# FMC_connector.net
KiCad netlist of a schematic drawn in Altium Designer
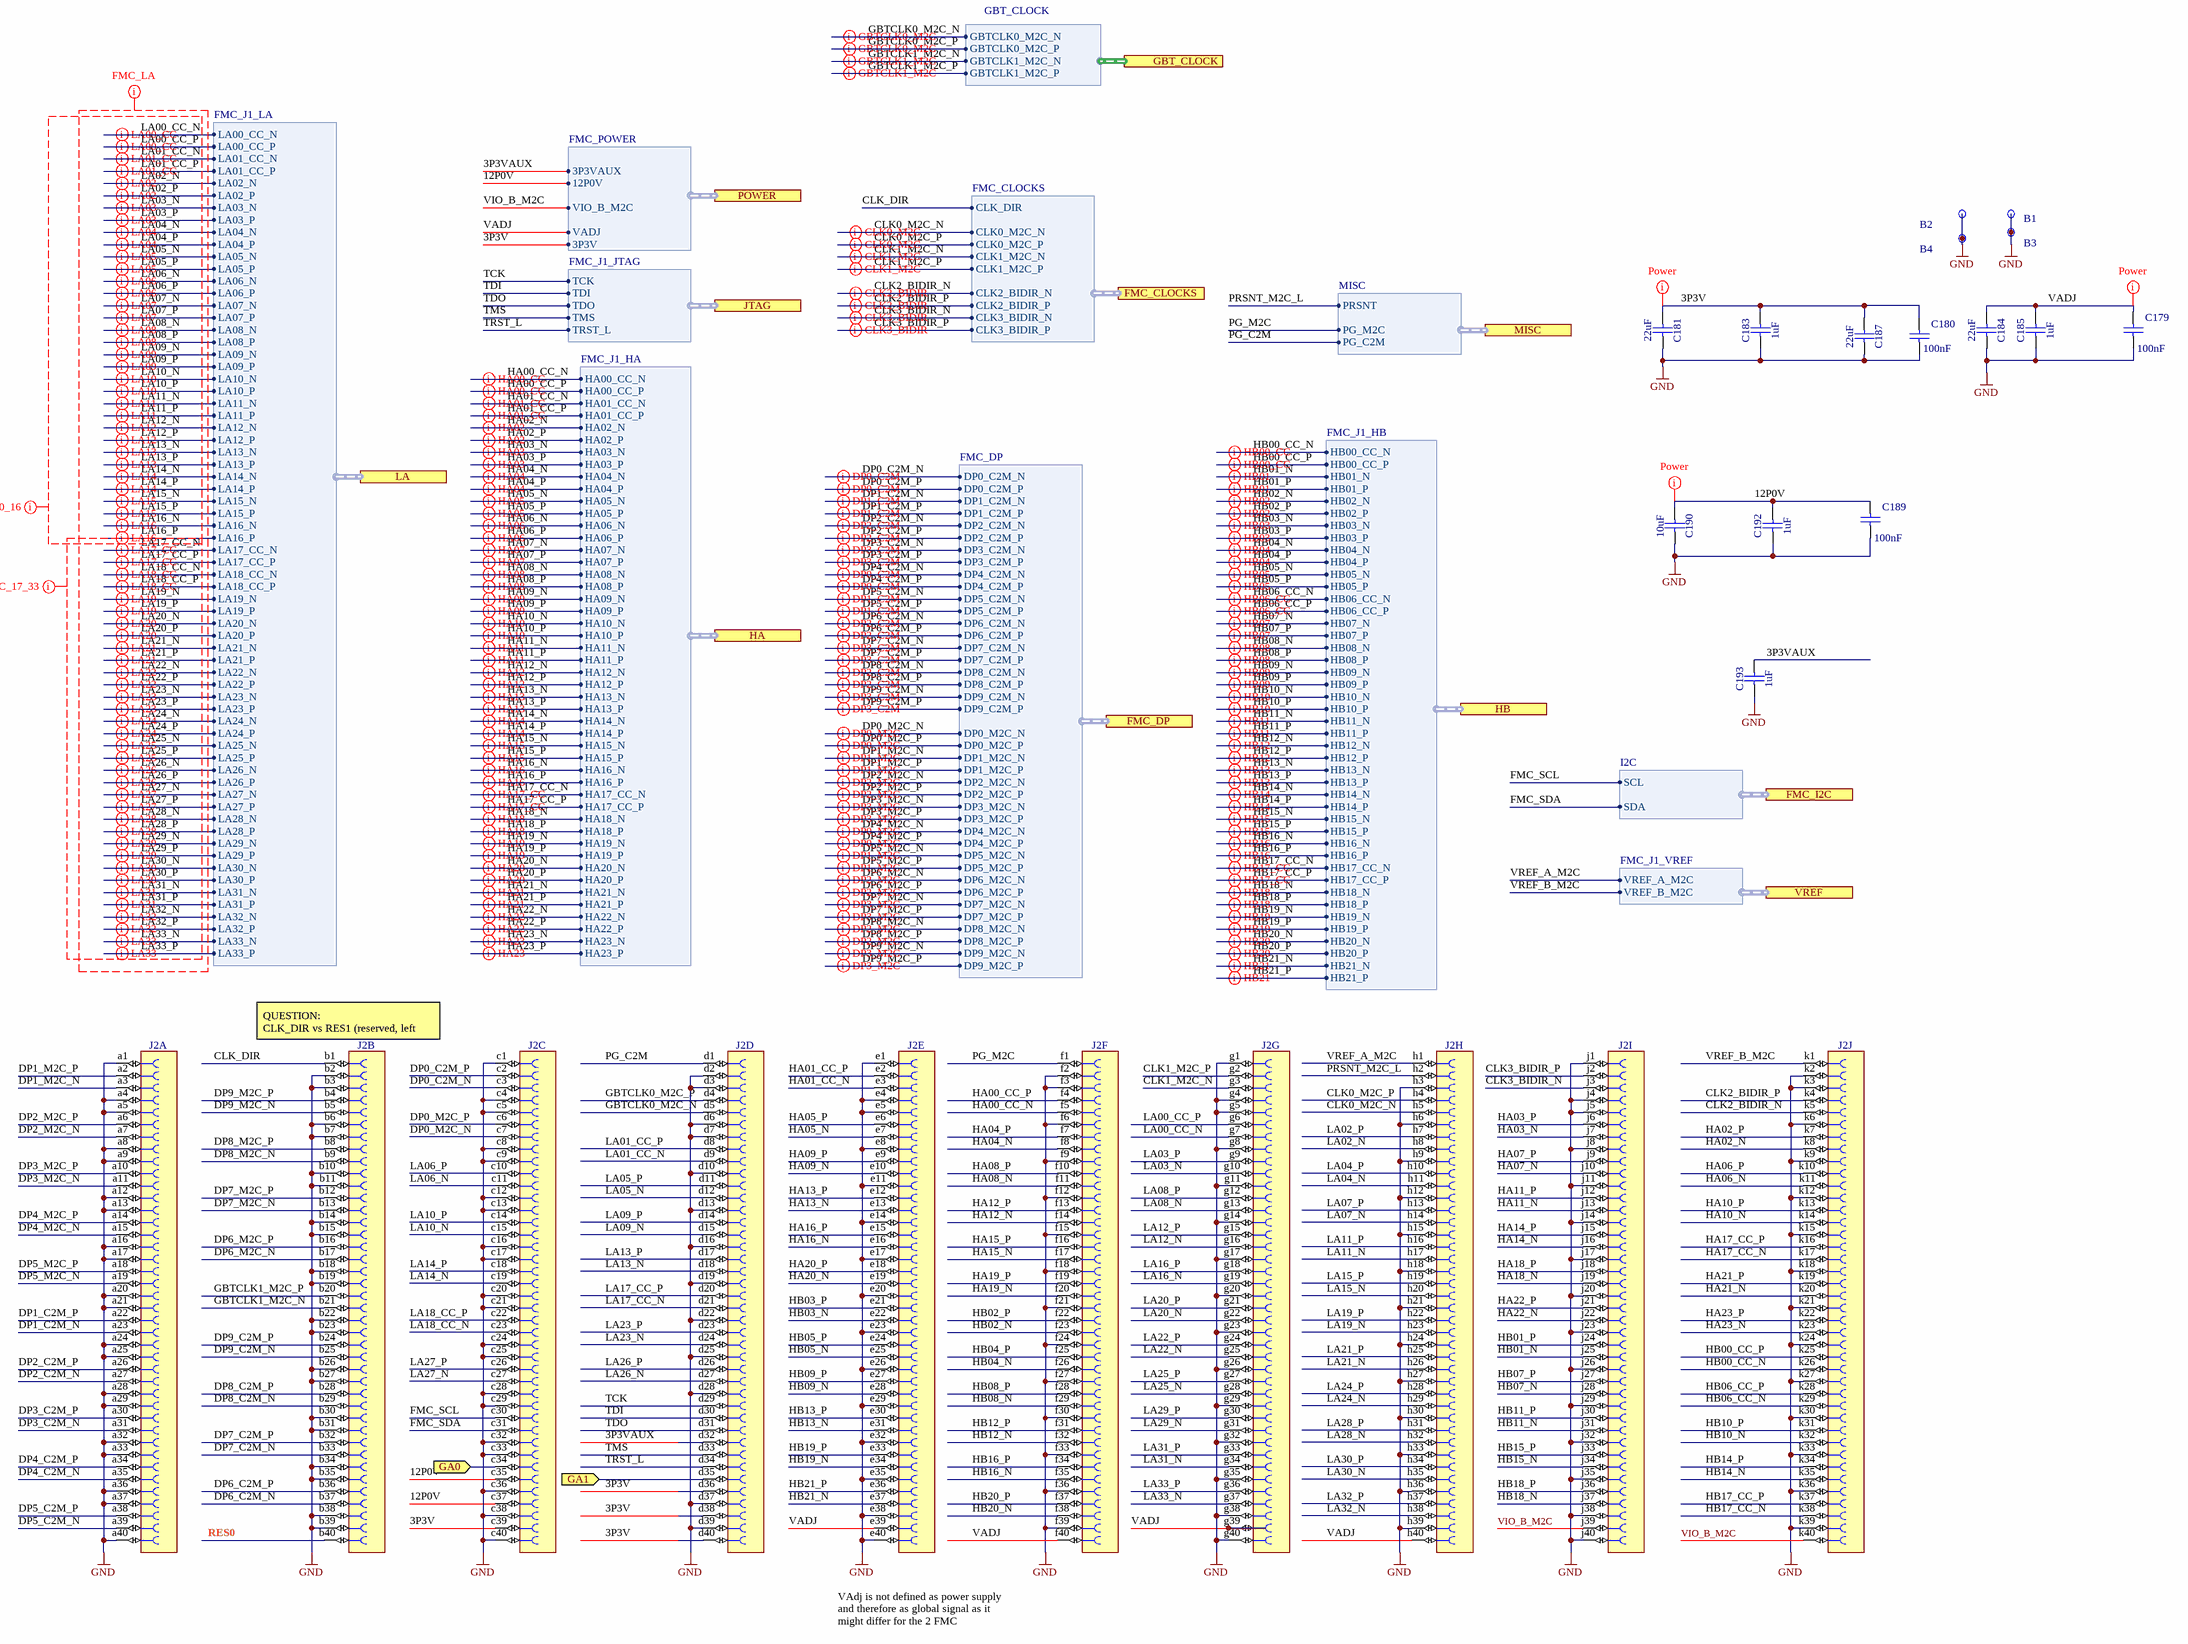
[diagram p0: FMC_connector.SchDoc]

(export (version "E")
  (design (tool "Eeschema 10.0.6"))
  (components
    (comp (ref "B1")
      (value "Plated Hole")
      (footprint "MTG270_500")
      (description "Single Terminal Socket")
      (fields (field (name "PART NUMBER") "PLATED_HOLE2.7_PAD5.0") (field (name "AUTHOR") "CERN DEM JMW"))
      (libsource (lib "Eletro-mechanical") (part "Single Terminal Socket"))
    )
    (comp (ref "B2")
      (value "Plated Hole")
      (footprint "MTG270_500")
      (description "Single Terminal Socket")
      (fields (field (name "PART NUMBER") "PLATED_HOLE2.7_PAD5.0") (field (name "AUTHOR") "CERN DEM JMW"))
      (libsource (lib "Eletro-mechanical") (part "Single Terminal Socket"))
    )
    (comp (ref "B3")
      (value "Plated Hole")
      (footprint "MTG270_500")
      (description "Single Terminal Socket")
      (fields (field (name "PART NUMBER") "PLATED_HOLE2.7_PAD5.0") (field (name "AUTHOR") "CERN DEM JMW"))
      (libsource (lib "Eletro-mechanical") (part "Single Terminal Socket"))
    )
    (comp (ref "B4")
      (value "Plated Hole")
      (footprint "MTG270_500")
      (description "Single Terminal Socket")
      (fields (field (name "PART NUMBER") "PLATED_HOLE2.7_PAD5.0") (field (name "AUTHOR") "CERN DEM JMW"))
      (libsource (lib "Eletro-mechanical") (part "Single Terminal Socket"))
    )
    (comp (ref "C179")
      (value "100nF")
      (footprint "CAPC0603X33N")
      (description "Non-polarised capacitor")
      (fields
        (field (name "PART NUMBER") "CC0201_100NF_6.3V_10%_X5R")
        (field (name "VOLTAGE") "6.3V")
        (field (name "AUTHOR") "CERN DEM JLC")
      )
      (libsource (lib "Capacitors") (part "Capacitor - non polarized"))
    )
    (comp (ref "C180")
      (value "100nF")
      (footprint "CAPC0603X33N")
      (description "Non-polarised capacitor")
      (fields
        (field (name "PART NUMBER") "CC0201_100NF_6.3V_10%_X5R")
        (field (name "VOLTAGE") "6.3V")
        (field (name "AUTHOR") "CERN DEM JLC")
      )
      (libsource (lib "Capacitors") (part "Capacitor - non polarized"))
    )
    (comp (ref "C181")
      (value "22uF")
      (footprint "CAPC3216X180N")
      (description "Non-polarised capacitor")
      (fields
        (field (name "PART NUMBER") "CC1206_22UF_10V_10%_X7R")
        (field (name "VOLTAGE") "10V")
        (field (name "AUTHOR") "CERN DEM JLC")
      )
      (libsource (lib "Capacitors") (part "Capacitor - non polarized"))
    )
    (comp (ref "C183")
      (value "1uF")
      (footprint "CAPC1608X87N")
      (description "Non-polarised capacitor")
      (fields
        (field (name "PART NUMBER") "CC0603_1UF_25V_10%_X7R")
        (field (name "VOLTAGE") "25V")
        (field (name "AUTHOR") "CERN DEM JLC")
      )
      (libsource (lib "Capacitors") (part "Capacitor - non polarized"))
    )
    (comp (ref "C184")
      (value "22uF")
      (footprint "CAPC3216X180N")
      (description "Non-polarised capacitor")
      (fields
        (field (name "PART NUMBER") "CC1206_22UF_10V_10%_X7R")
        (field (name "VOLTAGE") "10V")
        (field (name "AUTHOR") "CERN DEM JLC")
      )
      (libsource (lib "Capacitors") (part "Capacitor - non polarized"))
    )
    (comp (ref "C185")
      (value "1uF")
      (footprint "CAPC1608X87N")
      (description "Non-polarised capacitor")
      (fields
        (field (name "PART NUMBER") "CC0603_1UF_25V_10%_X7R")
        (field (name "VOLTAGE") "25V")
        (field (name "AUTHOR") "CERN DEM JLC")
      )
      (libsource (lib "Capacitors") (part "Capacitor - non polarized"))
    )
    (comp (ref "C187")
      (value "22uF")
      (footprint "CAPC3216X180N")
      (description "Non-polarised capacitor")
      (fields
        (field (name "PART NUMBER") "CC1206_22UF_10V_10%_X7R")
        (field (name "VOLTAGE") "10V")
        (field (name "AUTHOR") "CERN DEM JLC")
      )
      (libsource (lib "Capacitors") (part "Capacitor - non polarized"))
    )
    (comp (ref "C189")
      (value "100nF")
      (footprint "CAPC0603X33N")
      (description "Non-polarised capacitor")
      (fields
        (field (name "PART NUMBER") "CC0201_100NF_6.3V_10%_X5R")
        (field (name "VOLTAGE") "6.3V")
        (field (name "AUTHOR") "CERN DEM JLC")
      )
      (libsource (lib "Capacitors") (part "Capacitor - non polarized"))
    )
    (comp (ref "C190")
      (value "10uF")
      (footprint "CAPC2012X135N")
      (description "Non-polarised capacitor")
      (fields
        (field (name "PART NUMBER") "CC0805_10UF_16V_10%_X5R")
        (field (name "VOLTAGE") "16V")
        (field (name "AUTHOR") "CERN DEM JLC")
      )
      (libsource (lib "Capacitors") (part "Capacitor - non polarized"))
    )
    (comp (ref "C192")
      (value "1uF")
      (footprint "CAPC1608X87N")
      (description "Non-polarised capacitor")
      (fields
        (field (name "PART NUMBER") "CC0603_1UF_25V_10%_X7R")
        (field (name "VOLTAGE") "25V")
        (field (name "AUTHOR") "CERN DEM JLC")
      )
      (libsource (lib "Capacitors") (part "Capacitor - non polarized"))
    )
    (comp (ref "C193")
      (value "1uF")
      (footprint "CAPC1608X87N")
      (description "Non-polarised capacitor")
      (fields
        (field (name "PART NUMBER") "CC0603_1UF_25V_10%_X7R")
        (field (name "VOLTAGE") "25V")
        (field (name "AUTHOR") "CERN DEM JLC")
      )
      (libsource (lib "Capacitors") (part "Capacitor - non polarized"))
    )
    (comp (ref "J2")
      (value "VITA 57")
      (footprint "SAMTEC_ASP-134486-01")
      (description "Connector VITA 57, 400 Female contacts in 10 row abcdefghj")
      (fields
        (field (name "PART NUMBER") "SAMTEC_ASP-134486-01")
        (field (name "MANUFACTURER") "SAMTEC")
        (field (name "AUTHOR") "CERN DEM JLC")
      )
      (libsource (lib "Connectors") (part "Connector VITA 57 400 Female (abcdefghjk)"))
    )
  )
  (nets
    (net (code "12") (name "/3P3V") (class "Default")
      (node (ref "C180") (pin "2") (pinfunction "2_2") (pintype "passive"))
      (node (ref "C181") (pin "1") (pinfunction "1_1") (pintype "passive"))
      (node (ref "C183") (pin "2") (pinfunction "2_2") (pintype "passive"))
      (node (ref "C187") (pin "1") (pinfunction "1_1") (pintype "passive"))
      (node (ref "J2") (pin "c39") (pinfunction "c39_c39") (pintype "bidirectional"))
      (node (ref "J2") (pin "d36") (pinfunction "d36_d36") (pintype "bidirectional"))
      (node (ref "J2") (pin "d38") (pinfunction "d38_d38") (pintype "bidirectional"))
      (node (ref "J2") (pin "d40") (pinfunction "d40_d40") (pintype "bidirectional"))
    )
    (net (code "13") (name "/3P3VAUX") (class "Default")
      (node (ref "C193") (pin "2") (pinfunction "2_2") (pintype "passive"))
      (node (ref "J2") (pin "d32") (pinfunction "d32_d32") (pintype "bidirectional"))
    )
    (net (code "14") (name "/12P0V") (class "Default")
      (node (ref "C189") (pin "2") (pinfunction "2_2") (pintype "passive"))
      (node (ref "C190") (pin "1") (pinfunction "1_1") (pintype "passive"))
      (node (ref "C192") (pin "2") (pinfunction "2_2") (pintype "passive"))
      (node (ref "J2") (pin "c35") (pinfunction "c35_c35") (pintype "bidirectional"))
      (node (ref "J2") (pin "c37") (pinfunction "c37_c37") (pintype "bidirectional"))
    )
    (net (code "15") (name "/CLK0_M2C_N") (class "Default")
      (node (ref "J2") (pin "h5") (pinfunction "h5_h5") (pintype "bidirectional"))
    )
    (net (code "16") (name "/CLK0_M2C_P") (class "Default")
      (node (ref "J2") (pin "h4") (pinfunction "h4_h4") (pintype "bidirectional"))
    )
    (net (code "17") (name "/CLK1_M2C_N") (class "Default")
      (node (ref "J2") (pin "g3") (pinfunction "g3_g3") (pintype "bidirectional"))
    )
    (net (code "18") (name "/CLK1_M2C_P") (class "Default")
      (node (ref "J2") (pin "g2") (pinfunction "g2_g2") (pintype "bidirectional"))
    )
    (net (code "19") (name "/CLK2_BIDIR_N") (class "Default")
      (node (ref "J2") (pin "k5") (pinfunction "k5_k5") (pintype "bidirectional"))
    )
    (net (code "20") (name "/CLK2_BIDIR_P") (class "Default")
      (node (ref "J2") (pin "k4") (pinfunction "k4_k4") (pintype "bidirectional"))
    )
    (net (code "21") (name "/CLK3_BIDIR_N") (class "Default")
      (node (ref "J2") (pin "j3") (pinfunction "j3_j3") (pintype "bidirectional"))
    )
    (net (code "22") (name "/CLK3_BIDIR_P") (class "Default")
      (node (ref "J2") (pin "j2") (pinfunction "j2_j2") (pintype "bidirectional"))
    )
    (net (code "23") (name "/CLK_DIR") (class "Default")
      (node (ref "J2") (pin "b1") (pinfunction "b1_b1") (pintype "bidirectional"))
    )
    (net (code "24") (name "/DP0_C2M_N") (class "Default")
      (node (ref "J2") (pin "c3") (pinfunction "c3_c3") (pintype "bidirectional"))
    )
    (net (code "25") (name "/DP0_C2M_P") (class "Default")
      (node (ref "J2") (pin "c2") (pinfunction "c2_c2") (pintype "bidirectional"))
    )
    (net (code "26") (name "/DP0_M2C_N") (class "Default")
      (node (ref "J2") (pin "c7") (pinfunction "c7_c7") (pintype "bidirectional"))
    )
    (net (code "27") (name "/DP0_M2C_P") (class "Default")
      (node (ref "J2") (pin "c6") (pinfunction "c6_c6") (pintype "bidirectional"))
    )
    (net (code "28") (name "/DP1_C2M_N") (class "Default")
      (node (ref "J2") (pin "a23") (pinfunction "a23_a23") (pintype "bidirectional"))
    )
    (net (code "29") (name "/DP1_C2M_P") (class "Default")
      (node (ref "J2") (pin "a22") (pinfunction "a22_a22") (pintype "bidirectional"))
    )
    (net (code "30") (name "/DP1_M2C_N") (class "Default")
      (node (ref "J2") (pin "a3") (pinfunction "a3_a3") (pintype "bidirectional"))
    )
    (net (code "31") (name "/DP1_M2C_P") (class "Default")
      (node (ref "J2") (pin "a2") (pinfunction "a2_a2") (pintype "bidirectional"))
    )
    (net (code "32") (name "/DP2_C2M_N") (class "Default")
      (node (ref "J2") (pin "a27") (pinfunction "a27_a27") (pintype "bidirectional"))
    )
    (net (code "33") (name "/DP2_C2M_P") (class "Default")
      (node (ref "J2") (pin "a26") (pinfunction "a26_a26") (pintype "bidirectional"))
    )
    (net (code "34") (name "/DP2_M2C_N") (class "Default")
      (node (ref "J2") (pin "a7") (pinfunction "a7_a7") (pintype "bidirectional"))
    )
    (net (code "35") (name "/DP2_M2C_P") (class "Default")
      (node (ref "J2") (pin "a6") (pinfunction "a6_a6") (pintype "bidirectional"))
    )
    (net (code "36") (name "/DP3_C2M_N") (class "Default")
      (node (ref "J2") (pin "a31") (pinfunction "a31_a31") (pintype "bidirectional"))
    )
    (net (code "37") (name "/DP3_C2M_P") (class "Default")
      (node (ref "J2") (pin "a30") (pinfunction "a30_a30") (pintype "bidirectional"))
    )
    (net (code "38") (name "/DP3_M2C_N") (class "Default")
      (node (ref "J2") (pin "a11") (pinfunction "a11_a11") (pintype "bidirectional"))
    )
    (net (code "39") (name "/DP3_M2C_P") (class "Default")
      (node (ref "J2") (pin "a10") (pinfunction "a10_a10") (pintype "bidirectional"))
    )
    (net (code "40") (name "/DP4_C2M_N") (class "Default")
      (node (ref "J2") (pin "a35") (pinfunction "a35_a35") (pintype "bidirectional"))
    )
    (net (code "41") (name "/DP4_C2M_P") (class "Default")
      (node (ref "J2") (pin "a34") (pinfunction "a34_a34") (pintype "bidirectional"))
    )
    (net (code "42") (name "/DP4_M2C_N") (class "Default")
      (node (ref "J2") (pin "a15") (pinfunction "a15_a15") (pintype "bidirectional"))
    )
    (net (code "43") (name "/DP4_M2C_P") (class "Default")
      (node (ref "J2") (pin "a14") (pinfunction "a14_a14") (pintype "bidirectional"))
    )
    (net (code "44") (name "/DP5_C2M_N") (class "Default")
      (node (ref "J2") (pin "a39") (pinfunction "a39_a39") (pintype "bidirectional"))
    )
    (net (code "45") (name "/DP5_C2M_P") (class "Default")
      (node (ref "J2") (pin "a38") (pinfunction "a38_a38") (pintype "bidirectional"))
    )
    (net (code "46") (name "/DP5_M2C_N") (class "Default")
      (node (ref "J2") (pin "a19") (pinfunction "a19_a19") (pintype "bidirectional"))
    )
    (net (code "47") (name "/DP5_M2C_P") (class "Default")
      (node (ref "J2") (pin "a18") (pinfunction "a18_a18") (pintype "bidirectional"))
    )
    (net (code "48") (name "/DP6_C2M_N") (class "Default")
      (node (ref "J2") (pin "b37") (pinfunction "b37_b37") (pintype "bidirectional"))
    )
    (net (code "49") (name "/DP6_C2M_P") (class "Default")
      (node (ref "J2") (pin "b36") (pinfunction "b36_b36") (pintype "bidirectional"))
    )
    (net (code "50") (name "/DP6_M2C_N") (class "Default")
      (node (ref "J2") (pin "b17") (pinfunction "b17_b17") (pintype "bidirectional"))
    )
    (net (code "51") (name "/DP6_M2C_P") (class "Default")
      (node (ref "J2") (pin "b16") (pinfunction "b16_b16") (pintype "bidirectional"))
    )
    (net (code "52") (name "/DP7_C2M_N") (class "Default")
      (node (ref "J2") (pin "b33") (pinfunction "b33_b33") (pintype "bidirectional"))
    )
    (net (code "53") (name "/DP7_C2M_P") (class "Default")
      (node (ref "J2") (pin "b32") (pinfunction "b32_b32") (pintype "bidirectional"))
    )
    (net (code "54") (name "/DP7_M2C_N") (class "Default")
      (node (ref "J2") (pin "b13") (pinfunction "b13_b13") (pintype "bidirectional"))
    )
    (net (code "55") (name "/DP7_M2C_P") (class "Default")
      (node (ref "J2") (pin "b12") (pinfunction "b12_b12") (pintype "bidirectional"))
    )
    (net (code "56") (name "/DP8_C2M_N") (class "Default")
      (node (ref "J2") (pin "b29") (pinfunction "b29_b29") (pintype "bidirectional"))
    )
    (net (code "57") (name "/DP8_C2M_P") (class "Default")
      (node (ref "J2") (pin "b28") (pinfunction "b28_b28") (pintype "bidirectional"))
    )
    (net (code "58") (name "/DP8_M2C_N") (class "Default")
      (node (ref "J2") (pin "b9") (pinfunction "b9_b9") (pintype "bidirectional"))
    )
    (net (code "59") (name "/DP8_M2C_P") (class "Default")
      (node (ref "J2") (pin "b8") (pinfunction "b8_b8") (pintype "bidirectional"))
    )
    (net (code "60") (name "/DP9_C2M_N") (class "Default")
      (node (ref "J2") (pin "b25") (pinfunction "b25_b25") (pintype "bidirectional"))
    )
    (net (code "61") (name "/DP9_C2M_P") (class "Default")
      (node (ref "J2") (pin "b24") (pinfunction "b24_b24") (pintype "bidirectional"))
    )
    (net (code "62") (name "/DP9_M2C_N") (class "Default")
      (node (ref "J2") (pin "b5") (pinfunction "b5_b5") (pintype "bidirectional"))
    )
    (net (code "63") (name "/DP9_M2C_P") (class "Default")
      (node (ref "J2") (pin "b4") (pinfunction "b4_b4") (pintype "bidirectional"))
    )
    (net (code "64") (name "/FMC_SCL") (class "Default")
      (node (ref "J2") (pin "c30") (pinfunction "c30_c30") (pintype "bidirectional"))
    )
    (net (code "65") (name "/FMC_SDA") (class "Default")
      (node (ref "J2") (pin "c31") (pinfunction "c31_c31") (pintype "bidirectional"))
    )
    (net (code "66") (name "/GA0") (class "Default")
      (node (ref "J2") (pin "c34") (pinfunction "c34_c34") (pintype "bidirectional"))
    )
    (net (code "67") (name "/GA1") (class "Default")
      (node (ref "J2") (pin "d35") (pinfunction "d35_d35") (pintype "bidirectional"))
    )
    (net (code "68") (name "/GBTCLK0_M2C_N") (class "Default")
      (node (ref "J2") (pin "d5") (pinfunction "d5_d5") (pintype "bidirectional"))
    )
    (net (code "69") (name "/GBTCLK0_M2C_P") (class "Default")
      (node (ref "J2") (pin "d4") (pinfunction "d4_d4") (pintype "bidirectional"))
    )
    (net (code "70") (name "/GBTCLK1_M2C_N") (class "Default")
      (node (ref "J2") (pin "b21") (pinfunction "b21_b21") (pintype "bidirectional"))
    )
    (net (code "71") (name "/GBTCLK1_M2C_P") (class "Default")
      (node (ref "J2") (pin "b20") (pinfunction "b20_b20") (pintype "bidirectional"))
    )
    (net (code "72") (name "/HA00_CC_N") (class "Default")
      (node (ref "J2") (pin "f5") (pinfunction "f5_f5") (pintype "bidirectional"))
    )
    (net (code "73") (name "/HA00_CC_P") (class "Default")
      (node (ref "J2") (pin "f4") (pinfunction "f4_f4") (pintype "bidirectional"))
    )
    (net (code "74") (name "/HA01_CC_N") (class "Default")
      (node (ref "J2") (pin "e3") (pinfunction "e3_e3") (pintype "bidirectional"))
    )
    (net (code "75") (name "/HA01_CC_P") (class "Default")
      (node (ref "J2") (pin "e2") (pinfunction "e2_e2") (pintype "bidirectional"))
    )
    (net (code "76") (name "/HA02_N") (class "Default")
      (node (ref "J2") (pin "k8") (pinfunction "k8_k8") (pintype "bidirectional"))
    )
    (net (code "77") (name "/HA02_P") (class "Default")
      (node (ref "J2") (pin "k7") (pinfunction "k7_k7") (pintype "bidirectional"))
    )
    (net (code "78") (name "/HA03_N") (class "Default")
      (node (ref "J2") (pin "j7") (pinfunction "j7_j7") (pintype "bidirectional"))
    )
    (net (code "79") (name "/HA03_P") (class "Default")
      (node (ref "J2") (pin "j6") (pinfunction "j6_j6") (pintype "bidirectional"))
    )
    (net (code "80") (name "/HA04_N") (class "Default")
      (node (ref "J2") (pin "f8") (pinfunction "f8_f8") (pintype "bidirectional"))
    )
    (net (code "81") (name "/HA04_P") (class "Default")
      (node (ref "J2") (pin "f7") (pinfunction "f7_f7") (pintype "bidirectional"))
    )
    (net (code "82") (name "/HA05_N") (class "Default")
      (node (ref "J2") (pin "e7") (pinfunction "e7_e7") (pintype "bidirectional"))
    )
    (net (code "83") (name "/HA05_P") (class "Default")
      (node (ref "J2") (pin "e6") (pinfunction "e6_e6") (pintype "bidirectional"))
    )
    (net (code "84") (name "/HA06_N") (class "Default")
      (node (ref "J2") (pin "k11") (pinfunction "k11_k11") (pintype "bidirectional"))
    )
    (net (code "85") (name "/HA06_P") (class "Default")
      (node (ref "J2") (pin "k10") (pinfunction "k10_k10") (pintype "bidirectional"))
    )
    (net (code "86") (name "/HA07_N") (class "Default")
      (node (ref "J2") (pin "j10") (pinfunction "j10_j10") (pintype "bidirectional"))
    )
    (net (code "87") (name "/HA07_P") (class "Default")
      (node (ref "J2") (pin "j9") (pinfunction "j9_j9") (pintype "bidirectional"))
    )
    (net (code "88") (name "/HA08_N") (class "Default")
      (node (ref "J2") (pin "f11") (pinfunction "f11_f11") (pintype "bidirectional"))
    )
    (net (code "89") (name "/HA08_P") (class "Default")
      (node (ref "J2") (pin "f10") (pinfunction "f10_f10") (pintype "bidirectional"))
    )
    (net (code "90") (name "/HA09_N") (class "Default")
      (node (ref "J2") (pin "e10") (pinfunction "e10_e10") (pintype "bidirectional"))
    )
    (net (code "91") (name "/HA09_P") (class "Default")
      (node (ref "J2") (pin "e9") (pinfunction "e9_e9") (pintype "bidirectional"))
    )
    (net (code "92") (name "/HA10_N") (class "Default")
      (node (ref "J2") (pin "k14") (pinfunction "k14_k14") (pintype "bidirectional"))
    )
    (net (code "93") (name "/HA10_P") (class "Default")
      (node (ref "J2") (pin "k13") (pinfunction "k13_k13") (pintype "bidirectional"))
    )
    (net (code "94") (name "/HA11_N") (class "Default")
      (node (ref "J2") (pin "j13") (pinfunction "j13_j13") (pintype "bidirectional"))
    )
    (net (code "95") (name "/HA11_P") (class "Default")
      (node (ref "J2") (pin "j12") (pinfunction "j12_j12") (pintype "bidirectional"))
    )
    (net (code "96") (name "/HA12_N") (class "Default")
      (node (ref "J2") (pin "f14") (pinfunction "f14_f14") (pintype "bidirectional"))
    )
    (net (code "97") (name "/HA12_P") (class "Default")
      (node (ref "J2") (pin "f13") (pinfunction "f13_f13") (pintype "bidirectional"))
    )
    (net (code "98") (name "/HA13_N") (class "Default")
      (node (ref "J2") (pin "e13") (pinfunction "e13_e13") (pintype "bidirectional"))
    )
    (net (code "99") (name "/HA13_P") (class "Default")
      (node (ref "J2") (pin "e12") (pinfunction "e12_e12") (pintype "bidirectional"))
    )
    (net (code "100") (name "/HA14_N") (class "Default")
      (node (ref "J2") (pin "j16") (pinfunction "j16_j16") (pintype "bidirectional"))
    )
    (net (code "101") (name "/HA14_P") (class "Default")
      (node (ref "J2") (pin "j15") (pinfunction "j15_j15") (pintype "bidirectional"))
    )
    (net (code "102") (name "/HA15_N") (class "Default")
      (node (ref "J2") (pin "f17") (pinfunction "f17_f17") (pintype "bidirectional"))
    )
    (net (code "103") (name "/HA15_P") (class "Default")
      (node (ref "J2") (pin "f16") (pinfunction "f16_f16") (pintype "bidirectional"))
    )
    (net (code "104") (name "/HA16_N") (class "Default")
      (node (ref "J2") (pin "e16") (pinfunction "e16_e16") (pintype "bidirectional"))
    )
    (net (code "105") (name "/HA16_P") (class "Default")
      (node (ref "J2") (pin "e15") (pinfunction "e15_e15") (pintype "bidirectional"))
    )
    (net (code "106") (name "/HA17_CC_N") (class "Default")
      (node (ref "J2") (pin "k17") (pinfunction "k17_k17") (pintype "bidirectional"))
    )
    (net (code "107") (name "/HA17_CC_P") (class "Default")
      (node (ref "J2") (pin "k16") (pinfunction "k16_k16") (pintype "bidirectional"))
    )
    (net (code "108") (name "/HA18_N") (class "Default")
      (node (ref "J2") (pin "j19") (pinfunction "j19_j19") (pintype "bidirectional"))
    )
    (net (code "109") (name "/HA18_P") (class "Default")
      (node (ref "J2") (pin "j18") (pinfunction "j18_j18") (pintype "bidirectional"))
    )
    (net (code "110") (name "/HA19_N") (class "Default")
      (node (ref "J2") (pin "f20") (pinfunction "f20_f20") (pintype "bidirectional"))
    )
    (net (code "111") (name "/HA19_P") (class "Default")
      (node (ref "J2") (pin "f19") (pinfunction "f19_f19") (pintype "bidirectional"))
    )
    (net (code "112") (name "/HA20_N") (class "Default")
      (node (ref "J2") (pin "e19") (pinfunction "e19_e19") (pintype "bidirectional"))
    )
    (net (code "113") (name "/HA20_P") (class "Default")
      (node (ref "J2") (pin "e18") (pinfunction "e18_e18") (pintype "bidirectional"))
    )
    (net (code "114") (name "/HA21_N") (class "Default")
      (node (ref "J2") (pin "k20") (pinfunction "k20_k20") (pintype "bidirectional"))
    )
    (net (code "115") (name "/HA21_P") (class "Default")
      (node (ref "J2") (pin "k19") (pinfunction "k19_k19") (pintype "bidirectional"))
    )
    (net (code "116") (name "/HA22_N") (class "Default")
      (node (ref "J2") (pin "j22") (pinfunction "j22_j22") (pintype "bidirectional"))
    )
    (net (code "117") (name "/HA22_P") (class "Default")
      (node (ref "J2") (pin "j21") (pinfunction "j21_j21") (pintype "bidirectional"))
    )
    (net (code "118") (name "/HA23_N") (class "Default")
      (node (ref "J2") (pin "k23") (pinfunction "k23_k23") (pintype "bidirectional"))
    )
    (net (code "119") (name "/HA23_P") (class "Default")
      (node (ref "J2") (pin "k22") (pinfunction "k22_k22") (pintype "bidirectional"))
    )
    (net (code "120") (name "/HB00_CC_N") (class "Default")
      (node (ref "J2") (pin "k26") (pinfunction "k26_k26") (pintype "bidirectional"))
    )
    (net (code "121") (name "/HB00_CC_P") (class "Default")
      (node (ref "J2") (pin "k25") (pinfunction "k25_k25") (pintype "bidirectional"))
    )
    (net (code "122") (name "/HB01_N") (class "Default")
      (node (ref "J2") (pin "j25") (pinfunction "j25_j25") (pintype "bidirectional"))
    )
    (net (code "123") (name "/HB01_P") (class "Default")
      (node (ref "J2") (pin "j24") (pinfunction "j24_j24") (pintype "bidirectional"))
    )
    (net (code "124") (name "/HB02_N") (class "Default")
      (node (ref "J2") (pin "f23") (pinfunction "f23_f23") (pintype "bidirectional"))
    )
    (net (code "125") (name "/HB02_P") (class "Default")
      (node (ref "J2") (pin "f22") (pinfunction "f22_f22") (pintype "bidirectional"))
    )
    (net (code "126") (name "/HB03_N") (class "Default")
      (node (ref "J2") (pin "e22") (pinfunction "e22_e22") (pintype "bidirectional"))
    )
    (net (code "127") (name "/HB03_P") (class "Default")
      (node (ref "J2") (pin "e21") (pinfunction "e21_e21") (pintype "bidirectional"))
    )
    (net (code "128") (name "/HB04_N") (class "Default")
      (node (ref "J2") (pin "f26") (pinfunction "f26_f26") (pintype "bidirectional"))
    )
    (net (code "129") (name "/HB04_P") (class "Default")
      (node (ref "J2") (pin "f25") (pinfunction "f25_f25") (pintype "bidirectional"))
    )
    (net (code "130") (name "/HB05_N") (class "Default")
      (node (ref "J2") (pin "e25") (pinfunction "e25_e25") (pintype "bidirectional"))
    )
    (net (code "131") (name "/HB05_P") (class "Default")
      (node (ref "J2") (pin "e24") (pinfunction "e24_e24") (pintype "bidirectional"))
    )
    (net (code "132") (name "/HB06_CC_N") (class "Default")
      (node (ref "J2") (pin "k29") (pinfunction "k29_k29") (pintype "bidirectional"))
    )
    (net (code "133") (name "/HB06_CC_P") (class "Default")
      (node (ref "J2") (pin "k28") (pinfunction "k28_k28") (pintype "bidirectional"))
    )
    (net (code "134") (name "/HB07_N") (class "Default")
      (node (ref "J2") (pin "j28") (pinfunction "j28_j28") (pintype "bidirectional"))
    )
    (net (code "135") (name "/HB07_P") (class "Default")
      (node (ref "J2") (pin "j27") (pinfunction "j27_j27") (pintype "bidirectional"))
    )
    (net (code "136") (name "/HB08_N") (class "Default")
      (node (ref "J2") (pin "f29") (pinfunction "f29_f29") (pintype "bidirectional"))
    )
    (net (code "137") (name "/HB08_P") (class "Default")
      (node (ref "J2") (pin "f28") (pinfunction "f28_f28") (pintype "bidirectional"))
    )
    (net (code "138") (name "/HB09_N") (class "Default")
      (node (ref "J2") (pin "e28") (pinfunction "e28_e28") (pintype "bidirectional"))
    )
    (net (code "139") (name "/HB09_P") (class "Default")
      (node (ref "J2") (pin "e27") (pinfunction "e27_e27") (pintype "bidirectional"))
    )
    (net (code "140") (name "/HB10_N") (class "Default")
      (node (ref "J2") (pin "k32") (pinfunction "k32_k32") (pintype "bidirectional"))
    )
    (net (code "141") (name "/HB10_P") (class "Default")
      (node (ref "J2") (pin "k31") (pinfunction "k31_k31") (pintype "bidirectional"))
    )
    (net (code "142") (name "/HB11_N") (class "Default")
      (node (ref "J2") (pin "j31") (pinfunction "j31_j31") (pintype "bidirectional"))
    )
    (net (code "143") (name "/HB11_P") (class "Default")
      (node (ref "J2") (pin "j30") (pinfunction "j30_j30") (pintype "bidirectional"))
    )
    (net (code "144") (name "/HB12_N") (class "Default")
      (node (ref "J2") (pin "f32") (pinfunction "f32_f32") (pintype "bidirectional"))
    )
    (net (code "145") (name "/HB12_P") (class "Default")
      (node (ref "J2") (pin "f31") (pinfunction "f31_f31") (pintype "bidirectional"))
    )
    (net (code "146") (name "/HB13_N") (class "Default")
      (node (ref "J2") (pin "e31") (pinfunction "e31_e31") (pintype "bidirectional"))
    )
    (net (code "147") (name "/HB13_P") (class "Default")
      (node (ref "J2") (pin "e30") (pinfunction "e30_e30") (pintype "bidirectional"))
    )
    (net (code "148") (name "/HB14_N") (class "Default")
      (node (ref "J2") (pin "k35") (pinfunction "k35_k35") (pintype "bidirectional"))
    )
    (net (code "149") (name "/HB14_P") (class "Default")
      (node (ref "J2") (pin "k34") (pinfunction "k34_k34") (pintype "bidirectional"))
    )
    (net (code "150") (name "/HB15_N") (class "Default")
      (node (ref "J2") (pin "j34") (pinfunction "j34_j34") (pintype "bidirectional"))
    )
    (net (code "151") (name "/HB15_P") (class "Default")
      (node (ref "J2") (pin "j33") (pinfunction "j33_j33") (pintype "bidirectional"))
    )
    (net (code "152") (name "/HB16_N") (class "Default")
      (node (ref "J2") (pin "f35") (pinfunction "f35_f35") (pintype "bidirectional"))
    )
    (net (code "153") (name "/HB16_P") (class "Default")
      (node (ref "J2") (pin "f34") (pinfunction "f34_f34") (pintype "bidirectional"))
    )
    (net (code "154") (name "/HB17_CC_N") (class "Default")
      (node (ref "J2") (pin "k38") (pinfunction "k38_k38") (pintype "bidirectional"))
    )
    (net (code "155") (name "/HB17_CC_P") (class "Default")
      (node (ref "J2") (pin "k37") (pinfunction "k37_k37") (pintype "bidirectional"))
    )
    (net (code "156") (name "/HB18_N") (class "Default")
      (node (ref "J2") (pin "j37") (pinfunction "j37_j37") (pintype "bidirectional"))
    )
    (net (code "157") (name "/HB18_P") (class "Default")
      (node (ref "J2") (pin "j36") (pinfunction "j36_j36") (pintype "bidirectional"))
    )
    (net (code "158") (name "/HB19_N") (class "Default")
      (node (ref "J2") (pin "e34") (pinfunction "e34_e34") (pintype "bidirectional"))
    )
    (net (code "159") (name "/HB19_P") (class "Default")
      (node (ref "J2") (pin "e33") (pinfunction "e33_e33") (pintype "bidirectional"))
    )
    (net (code "160") (name "/HB20_N") (class "Default")
      (node (ref "J2") (pin "f38") (pinfunction "f38_f38") (pintype "bidirectional"))
    )
    (net (code "161") (name "/HB20_P") (class "Default")
      (node (ref "J2") (pin "f37") (pinfunction "f37_f37") (pintype "bidirectional"))
    )
    (net (code "162") (name "/HB21_N") (class "Default")
      (node (ref "J2") (pin "e37") (pinfunction "e37_e37") (pintype "bidirectional"))
    )
    (net (code "163") (name "/HB21_P") (class "Default")
      (node (ref "J2") (pin "e36") (pinfunction "e36_e36") (pintype "bidirectional"))
    )
    (net (code "164") (name "/LA00_CC_N") (class "Default")
      (node (ref "J2") (pin "g7") (pinfunction "g7_g7") (pintype "bidirectional"))
    )
    (net (code "165") (name "/LA00_CC_P") (class "Default")
      (node (ref "J2") (pin "g6") (pinfunction "g6_g6") (pintype "bidirectional"))
    )
    (net (code "166") (name "/LA01_CC_N") (class "Default")
      (node (ref "J2") (pin "d9") (pinfunction "d9_d9") (pintype "bidirectional"))
    )
    (net (code "167") (name "/LA01_CC_P") (class "Default")
      (node (ref "J2") (pin "d8") (pinfunction "d8_d8") (pintype "bidirectional"))
    )
    (net (code "168") (name "/LA02_N") (class "Default")
      (node (ref "J2") (pin "h8") (pinfunction "h8_h8") (pintype "bidirectional"))
    )
    (net (code "169") (name "/LA02_P") (class "Default")
      (node (ref "J2") (pin "h7") (pinfunction "h7_h7") (pintype "bidirectional"))
    )
    (net (code "170") (name "/LA03_N") (class "Default")
      (node (ref "J2") (pin "g10") (pinfunction "g10_g10") (pintype "bidirectional"))
    )
    (net (code "171") (name "/LA03_P") (class "Default")
      (node (ref "J2") (pin "g9") (pinfunction "g9_g9") (pintype "bidirectional"))
    )
    (net (code "172") (name "/LA04_N") (class "Default")
      (node (ref "J2") (pin "h11") (pinfunction "h11_h11") (pintype "bidirectional"))
    )
    (net (code "173") (name "/LA04_P") (class "Default")
      (node (ref "J2") (pin "h10") (pinfunction "h10_h10") (pintype "bidirectional"))
    )
    (net (code "174") (name "/LA05_N") (class "Default")
      (node (ref "J2") (pin "d12") (pinfunction "d12_d12") (pintype "bidirectional"))
    )
    (net (code "175") (name "/LA05_P") (class "Default")
      (node (ref "J2") (pin "d11") (pinfunction "d11_d11") (pintype "bidirectional"))
    )
    (net (code "176") (name "/LA06_N") (class "Default")
      (node (ref "J2") (pin "c11") (pinfunction "c11_c11") (pintype "bidirectional"))
    )
    (net (code "177") (name "/LA06_P") (class "Default")
      (node (ref "J2") (pin "c10") (pinfunction "c10_c10") (pintype "bidirectional"))
    )
    (net (code "178") (name "/LA07_N") (class "Default")
      (node (ref "J2") (pin "h14") (pinfunction "h14_h14") (pintype "bidirectional"))
    )
    (net (code "179") (name "/LA07_P") (class "Default")
      (node (ref "J2") (pin "h13") (pinfunction "h13_h13") (pintype "bidirectional"))
    )
    (net (code "180") (name "/LA08_N") (class "Default")
      (node (ref "J2") (pin "g13") (pinfunction "g13_g13") (pintype "bidirectional"))
    )
    (net (code "181") (name "/LA08_P") (class "Default")
      (node (ref "J2") (pin "g12") (pinfunction "g12_g12") (pintype "bidirectional"))
    )
    (net (code "182") (name "/LA09_N") (class "Default")
      (node (ref "J2") (pin "d15") (pinfunction "d15_d15") (pintype "bidirectional"))
    )
    (net (code "183") (name "/LA09_P") (class "Default")
      (node (ref "J2") (pin "d14") (pinfunction "d14_d14") (pintype "bidirectional"))
    )
    (net (code "184") (name "/LA10_N") (class "Default")
      (node (ref "J2") (pin "c15") (pinfunction "c15_c15") (pintype "bidirectional"))
    )
    (net (code "185") (name "/LA10_P") (class "Default")
      (node (ref "J2") (pin "c14") (pinfunction "c14_c14") (pintype "bidirectional"))
    )
    (net (code "186") (name "/LA11_N") (class "Default")
      (node (ref "J2") (pin "h17") (pinfunction "h17_h17") (pintype "bidirectional"))
    )
    (net (code "187") (name "/LA11_P") (class "Default")
      (node (ref "J2") (pin "h16") (pinfunction "h16_h16") (pintype "bidirectional"))
    )
    (net (code "188") (name "/LA12_N") (class "Default")
      (node (ref "J2") (pin "g16") (pinfunction "g16_g16") (pintype "bidirectional"))
    )
    (net (code "189") (name "/LA12_P") (class "Default")
      (node (ref "J2") (pin "g15") (pinfunction "g15_g15") (pintype "bidirectional"))
    )
    (net (code "190") (name "/LA13_N") (class "Default")
      (node (ref "J2") (pin "d18") (pinfunction "d18_d18") (pintype "bidirectional"))
    )
    (net (code "191") (name "/LA13_P") (class "Default")
      (node (ref "J2") (pin "d17") (pinfunction "d17_d17") (pintype "bidirectional"))
    )
    (net (code "192") (name "/LA14_N") (class "Default")
      (node (ref "J2") (pin "c19") (pinfunction "c19_c19") (pintype "bidirectional"))
    )
    (net (code "193") (name "/LA14_P") (class "Default")
      (node (ref "J2") (pin "c18") (pinfunction "c18_c18") (pintype "bidirectional"))
    )
    (net (code "194") (name "/LA15_N") (class "Default")
      (node (ref "J2") (pin "h20") (pinfunction "h20_h20") (pintype "bidirectional"))
    )
    (net (code "195") (name "/LA15_P") (class "Default")
      (node (ref "J2") (pin "h19") (pinfunction "h19_h19") (pintype "bidirectional"))
    )
    (net (code "196") (name "/LA16_N") (class "Default")
      (node (ref "J2") (pin "g19") (pinfunction "g19_g19") (pintype "bidirectional"))
    )
    (net (code "197") (name "/LA16_P") (class "Default")
      (node (ref "J2") (pin "g18") (pinfunction "g18_g18") (pintype "bidirectional"))
    )
    (net (code "198") (name "/LA17_CC_N") (class "Default")
      (node (ref "J2") (pin "d21") (pinfunction "d21_d21") (pintype "bidirectional"))
    )
    (net (code "199") (name "/LA17_CC_P") (class "Default")
      (node (ref "J2") (pin "d20") (pinfunction "d20_d20") (pintype "bidirectional"))
    )
    (net (code "200") (name "/LA18_CC_N") (class "Default")
      (node (ref "J2") (pin "c23") (pinfunction "c23_c23") (pintype "bidirectional"))
    )
    (net (code "201") (name "/LA18_CC_P") (class "Default")
      (node (ref "J2") (pin "c22") (pinfunction "c22_c22") (pintype "bidirectional"))
    )
    (net (code "202") (name "/LA19_N") (class "Default")
      (node (ref "J2") (pin "h23") (pinfunction "h23_h23") (pintype "bidirectional"))
    )
    (net (code "203") (name "/LA19_P") (class "Default")
      (node (ref "J2") (pin "h22") (pinfunction "h22_h22") (pintype "bidirectional"))
    )
    (net (code "204") (name "/LA20_N") (class "Default")
      (node (ref "J2") (pin "g22") (pinfunction "g22_g22") (pintype "bidirectional"))
    )
    (net (code "205") (name "/LA20_P") (class "Default")
      (node (ref "J2") (pin "g21") (pinfunction "g21_g21") (pintype "bidirectional"))
    )
    (net (code "206") (name "/LA21_N") (class "Default")
      (node (ref "J2") (pin "h26") (pinfunction "h26_h26") (pintype "bidirectional"))
    )
    (net (code "207") (name "/LA21_P") (class "Default")
      (node (ref "J2") (pin "h25") (pinfunction "h25_h25") (pintype "bidirectional"))
    )
    (net (code "208") (name "/LA22_N") (class "Default")
      (node (ref "J2") (pin "g25") (pinfunction "g25_g25") (pintype "bidirectional"))
    )
    (net (code "209") (name "/LA22_P") (class "Default")
      (node (ref "J2") (pin "g24") (pinfunction "g24_g24") (pintype "bidirectional"))
    )
    (net (code "210") (name "/LA23_N") (class "Default")
      (node (ref "J2") (pin "d24") (pinfunction "d24_d24") (pintype "bidirectional"))
    )
    (net (code "211") (name "/LA23_P") (class "Default")
      (node (ref "J2") (pin "d23") (pinfunction "d23_d23") (pintype "bidirectional"))
    )
    (net (code "212") (name "/LA24_N") (class "Default")
      (node (ref "J2") (pin "h29") (pinfunction "h29_h29") (pintype "bidirectional"))
    )
    (net (code "213") (name "/LA24_P") (class "Default")
      (node (ref "J2") (pin "h28") (pinfunction "h28_h28") (pintype "bidirectional"))
    )
    (net (code "214") (name "/LA25_N") (class "Default")
      (node (ref "J2") (pin "g28") (pinfunction "g28_g28") (pintype "bidirectional"))
    )
    (net (code "215") (name "/LA25_P") (class "Default")
      (node (ref "J2") (pin "g27") (pinfunction "g27_g27") (pintype "bidirectional"))
    )
    (net (code "216") (name "/LA26_N") (class "Default")
      (node (ref "J2") (pin "d27") (pinfunction "d27_d27") (pintype "bidirectional"))
    )
    (net (code "217") (name "/LA26_P") (class "Default")
      (node (ref "J2") (pin "d26") (pinfunction "d26_d26") (pintype "bidirectional"))
    )
    (net (code "218") (name "/LA27_N") (class "Default")
      (node (ref "J2") (pin "c27") (pinfunction "c27_c27") (pintype "bidirectional"))
    )
    (net (code "219") (name "/LA27_P") (class "Default")
      (node (ref "J2") (pin "c26") (pinfunction "c26_c26") (pintype "bidirectional"))
    )
    (net (code "220") (name "/LA28_N") (class "Default")
      (node (ref "J2") (pin "h32") (pinfunction "h32_h32") (pintype "bidirectional"))
    )
    (net (code "221") (name "/LA28_P") (class "Default")
      (node (ref "J2") (pin "h31") (pinfunction "h31_h31") (pintype "bidirectional"))
    )
    (net (code "222") (name "/LA29_N") (class "Default")
      (node (ref "J2") (pin "g31") (pinfunction "g31_g31") (pintype "bidirectional"))
    )
    (net (code "223") (name "/LA29_P") (class "Default")
      (node (ref "J2") (pin "g30") (pinfunction "g30_g30") (pintype "bidirectional"))
    )
    (net (code "224") (name "/LA30_N") (class "Default")
      (node (ref "J2") (pin "h35") (pinfunction "h35_h35") (pintype "bidirectional"))
    )
    (net (code "225") (name "/LA30_P") (class "Default")
      (node (ref "J2") (pin "h34") (pinfunction "h34_h34") (pintype "bidirectional"))
    )
    (net (code "226") (name "/LA31_N") (class "Default")
      (node (ref "J2") (pin "g34") (pinfunction "g34_g34") (pintype "bidirectional"))
    )
    (net (code "227") (name "/LA31_P") (class "Default")
      (node (ref "J2") (pin "g33") (pinfunction "g33_g33") (pintype "bidirectional"))
    )
    (net (code "228") (name "/LA32_N") (class "Default")
      (node (ref "J2") (pin "h38") (pinfunction "h38_h38") (pintype "bidirectional"))
    )
    (net (code "229") (name "/LA32_P") (class "Default")
      (node (ref "J2") (pin "h37") (pinfunction "h37_h37") (pintype "bidirectional"))
    )
    (net (code "230") (name "/LA33_N") (class "Default")
      (node (ref "J2") (pin "g37") (pinfunction "g37_g37") (pintype "bidirectional"))
    )
    (net (code "231") (name "/LA33_P") (class "Default")
      (node (ref "J2") (pin "g36") (pinfunction "g36_g36") (pintype "bidirectional"))
    )
    (net (code "232") (name "/PG_C2M") (class "Default")
      (node (ref "J2") (pin "d1") (pinfunction "d1_d1") (pintype "bidirectional"))
    )
    (net (code "233") (name "/PG_M2C") (class "Default")
      (node (ref "J2") (pin "f1") (pinfunction "f1_f1") (pintype "bidirectional"))
    )
    (net (code "234") (name "/PRSNT_M2C_L") (class "Default")
      (node (ref "J2") (pin "h2") (pinfunction "h2_h2") (pintype "bidirectional"))
    )
    (net (code "235") (name "/TCK") (class "Default")
      (node (ref "J2") (pin "d29") (pinfunction "d29_d29") (pintype "bidirectional"))
    )
    (net (code "236") (name "/TDI") (class "Default")
      (node (ref "J2") (pin "d30") (pinfunction "d30_d30") (pintype "bidirectional"))
    )
    (net (code "237") (name "/TDO") (class "Default")
      (node (ref "J2") (pin "d31") (pinfunction "d31_d31") (pintype "bidirectional"))
    )
    (net (code "238") (name "/TMS") (class "Default")
      (node (ref "J2") (pin "d33") (pinfunction "d33_d33") (pintype "bidirectional"))
    )
    (net (code "239") (name "/TRST_L") (class "Default")
      (node (ref "J2") (pin "d34") (pinfunction "d34_d34") (pintype "bidirectional"))
    )
    (net (code "240") (name "/VADJ") (class "Default")
      (node (ref "C179") (pin "2") (pinfunction "2_2") (pintype "passive"))
      (node (ref "C184") (pin "1") (pinfunction "1_1") (pintype "passive"))
      (node (ref "C185") (pin "2") (pinfunction "2_2") (pintype "passive"))
      (node (ref "J2") (pin "e39") (pinfunction "e39_e39") (pintype "bidirectional"))
      (node (ref "J2") (pin "f40") (pinfunction "f40_f40") (pintype "bidirectional"))
      (node (ref "J2") (pin "g39") (pinfunction "g39_g39") (pintype "bidirectional"))
      (node (ref "J2") (pin "h40") (pinfunction "h40_h40") (pintype "bidirectional"))
    )
    (net (code "241") (name "/VIO_B_M2C") (class "Default")
      (node (ref "J2") (pin "j39") (pinfunction "j39_j39") (pintype "bidirectional"))
      (node (ref "J2") (pin "k40") (pinfunction "k40_k40") (pintype "bidirectional"))
    )
    (net (code "242") (name "/VREF_A_M2C") (class "Default")
      (node (ref "J2") (pin "h1") (pinfunction "h1_h1") (pintype "bidirectional"))
    )
    (net (code "243") (name "/VREF_B_M2C") (class "Default")
      (node (ref "J2") (pin "k1") (pinfunction "k1_k1") (pintype "bidirectional"))
    )
    (net (code "255") (name "GND") (class "Default")
      (node (ref "B1") (pin "1") (pinfunction "1_1") (pintype "bidirectional"))
      (node (ref "B2") (pin "1") (pinfunction "1_1") (pintype "bidirectional"))
      (node (ref "B3") (pin "1") (pinfunction "1_1") (pintype "bidirectional"))
      (node (ref "B4") (pin "1") (pinfunction "1_1") (pintype "bidirectional"))
      (node (ref "C179") (pin "1") (pinfunction "1_1") (pintype "passive"))
      (node (ref "C180") (pin "1") (pinfunction "1_1") (pintype "passive"))
      (node (ref "C181") (pin "2") (pinfunction "2_2") (pintype "passive"))
      (node (ref "C183") (pin "1") (pinfunction "1_1") (pintype "passive"))
      (node (ref "C184") (pin "2") (pinfunction "2_2") (pintype "passive"))
      (node (ref "C185") (pin "1") (pinfunction "1_1") (pintype "passive"))
      (node (ref "C187") (pin "2") (pinfunction "2_2") (pintype "passive"))
      (node (ref "C189") (pin "1") (pinfunction "1_1") (pintype "passive"))
      (node (ref "C190") (pin "2") (pinfunction "2_2") (pintype "passive"))
      (node (ref "C192") (pin "1") (pinfunction "1_1") (pintype "passive"))
      (node (ref "C193") (pin "1") (pinfunction "1_1") (pintype "passive"))
      (node (ref "J2") (pin "a1") (pinfunction "a1_a1") (pintype "bidirectional"))
      (node (ref "J2") (pin "a12") (pinfunction "a12_a12") (pintype "bidirectional"))
      (node (ref "J2") (pin "a13") (pinfunction "a13_a13") (pintype "bidirectional"))
      (node (ref "J2") (pin "a16") (pinfunction "a16_a16") (pintype "bidirectional"))
      (node (ref "J2") (pin "a17") (pinfunction "a17_a17") (pintype "bidirectional"))
      (node (ref "J2") (pin "a20") (pinfunction "a20_a20") (pintype "bidirectional"))
      (node (ref "J2") (pin "a21") (pinfunction "a21_a21") (pintype "bidirectional"))
      (node (ref "J2") (pin "a24") (pinfunction "a24_a24") (pintype "bidirectional"))
      (node (ref "J2") (pin "a25") (pinfunction "a25_a25") (pintype "bidirectional"))
      (node (ref "J2") (pin "a28") (pinfunction "a28_a28") (pintype "bidirectional"))
      (node (ref "J2") (pin "a29") (pinfunction "a29_a29") (pintype "bidirectional"))
      (node (ref "J2") (pin "a32") (pinfunction "a32_a32") (pintype "bidirectional"))
      (node (ref "J2") (pin "a33") (pinfunction "a33_a33") (pintype "bidirectional"))
      (node (ref "J2") (pin "a36") (pinfunction "a36_a36") (pintype "bidirectional"))
      (node (ref "J2") (pin "a37") (pinfunction "a37_a37") (pintype "bidirectional"))
      (node (ref "J2") (pin "a4") (pinfunction "a4_a4") (pintype "bidirectional"))
      (node (ref "J2") (pin "a40") (pinfunction "a40_a40") (pintype "bidirectional"))
      (node (ref "J2") (pin "a5") (pinfunction "a5_a5") (pintype "bidirectional"))
      (node (ref "J2") (pin "a8") (pinfunction "a8_a8") (pintype "bidirectional"))
      (node (ref "J2") (pin "a9") (pinfunction "a9_a9") (pintype "bidirectional"))
      (node (ref "J2") (pin "b10") (pinfunction "b10_b10") (pintype "bidirectional"))
      (node (ref "J2") (pin "b11") (pinfunction "b11_b11") (pintype "bidirectional"))
      (node (ref "J2") (pin "b14") (pinfunction "b14_b14") (pintype "bidirectional"))
      (node (ref "J2") (pin "b15") (pinfunction "b15_b15") (pintype "bidirectional"))
      (node (ref "J2") (pin "b18") (pinfunction "b18_b18") (pintype "bidirectional"))
      (node (ref "J2") (pin "b19") (pinfunction "b19_b19") (pintype "bidirectional"))
      (node (ref "J2") (pin "b2") (pinfunction "b2_b2") (pintype "bidirectional"))
      (node (ref "J2") (pin "b22") (pinfunction "b22_b22") (pintype "bidirectional"))
      (node (ref "J2") (pin "b23") (pinfunction "b23_b23") (pintype "bidirectional"))
      (node (ref "J2") (pin "b26") (pinfunction "b26_b26") (pintype "bidirectional"))
      (node (ref "J2") (pin "b27") (pinfunction "b27_b27") (pintype "bidirectional"))
      (node (ref "J2") (pin "b3") (pinfunction "b3_b3") (pintype "bidirectional"))
      (node (ref "J2") (pin "b30") (pinfunction "b30_b30") (pintype "bidirectional"))
      (node (ref "J2") (pin "b31") (pinfunction "b31_b31") (pintype "bidirectional"))
      (node (ref "J2") (pin "b34") (pinfunction "b34_b34") (pintype "bidirectional"))
      (node (ref "J2") (pin "b35") (pinfunction "b35_b35") (pintype "bidirectional"))
      (node (ref "J2") (pin "b38") (pinfunction "b38_b38") (pintype "bidirectional"))
      (node (ref "J2") (pin "b39") (pinfunction "b39_b39") (pintype "bidirectional"))
      (node (ref "J2") (pin "b6") (pinfunction "b6_b6") (pintype "bidirectional"))
      (node (ref "J2") (pin "b7") (pinfunction "b7_b7") (pintype "bidirectional"))
      (node (ref "J2") (pin "c1") (pinfunction "c1_c1") (pintype "bidirectional"))
      (node (ref "J2") (pin "c12") (pinfunction "c12_c12") (pintype "bidirectional"))
      (node (ref "J2") (pin "c13") (pinfunction "c13_c13") (pintype "bidirectional"))
      (node (ref "J2") (pin "c16") (pinfunction "c16_c16") (pintype "bidirectional"))
      (node (ref "J2") (pin "c17") (pinfunction "c17_c17") (pintype "bidirectional"))
      (node (ref "J2") (pin "c20") (pinfunction "c20_c20") (pintype "bidirectional"))
      (node (ref "J2") (pin "c21") (pinfunction "c21_c21") (pintype "bidirectional"))
      (node (ref "J2") (pin "c24") (pinfunction "c24_c24") (pintype "bidirectional"))
      (node (ref "J2") (pin "c25") (pinfunction "c25_c25") (pintype "bidirectional"))
      (node (ref "J2") (pin "c28") (pinfunction "c28_c28") (pintype "bidirectional"))
      (node (ref "J2") (pin "c29") (pinfunction "c29_c29") (pintype "bidirectional"))
      (node (ref "J2") (pin "c32") (pinfunction "c32_c32") (pintype "bidirectional"))
      (node (ref "J2") (pin "c33") (pinfunction "c33_c33") (pintype "bidirectional"))
      (node (ref "J2") (pin "c36") (pinfunction "c36_c36") (pintype "bidirectional"))
      (node (ref "J2") (pin "c38") (pinfunction "c38_c38") (pintype "bidirectional"))
      (node (ref "J2") (pin "c4") (pinfunction "c4_c4") (pintype "bidirectional"))
      (node (ref "J2") (pin "c40") (pinfunction "c40_c40") (pintype "bidirectional"))
      (node (ref "J2") (pin "c5") (pinfunction "c5_c5") (pintype "bidirectional"))
      (node (ref "J2") (pin "c8") (pinfunction "c8_c8") (pintype "bidirectional"))
      (node (ref "J2") (pin "c9") (pinfunction "c9_c9") (pintype "bidirectional"))
      (node (ref "J2") (pin "d10") (pinfunction "d10_d10") (pintype "bidirectional"))
      (node (ref "J2") (pin "d13") (pinfunction "d13_d13") (pintype "bidirectional"))
      (node (ref "J2") (pin "d16") (pinfunction "d16_d16") (pintype "bidirectional"))
      (node (ref "J2") (pin "d19") (pinfunction "d19_d19") (pintype "bidirectional"))
      (node (ref "J2") (pin "d2") (pinfunction "d2_d2") (pintype "bidirectional"))
      (node (ref "J2") (pin "d22") (pinfunction "d22_d22") (pintype "bidirectional"))
      (node (ref "J2") (pin "d25") (pinfunction "d25_d25") (pintype "bidirectional"))
      (node (ref "J2") (pin "d28") (pinfunction "d28_d28") (pintype "bidirectional"))
      (node (ref "J2") (pin "d3") (pinfunction "d3_d3") (pintype "bidirectional"))
      (node (ref "J2") (pin "d37") (pinfunction "d37_d37") (pintype "bidirectional"))
      (node (ref "J2") (pin "d39") (pinfunction "d39_d39") (pintype "bidirectional"))
      (node (ref "J2") (pin "d6") (pinfunction "d6_d6") (pintype "bidirectional"))
      (node (ref "J2") (pin "d7") (pinfunction "d7_d7") (pintype "bidirectional"))
      (node (ref "J2") (pin "e1") (pinfunction "e1_e1") (pintype "bidirectional"))
      (node (ref "J2") (pin "e11") (pinfunction "e11_e11") (pintype "bidirectional"))
      (node (ref "J2") (pin "e14") (pinfunction "e14_e14") (pintype "bidirectional"))
      (node (ref "J2") (pin "e17") (pinfunction "e17_e17") (pintype "bidirectional"))
      (node (ref "J2") (pin "e20") (pinfunction "e20_e20") (pintype "bidirectional"))
      (node (ref "J2") (pin "e23") (pinfunction "e23_e23") (pintype "bidirectional"))
      (node (ref "J2") (pin "e26") (pinfunction "e26_e26") (pintype "bidirectional"))
      (node (ref "J2") (pin "e29") (pinfunction "e29_e29") (pintype "bidirectional"))
      (node (ref "J2") (pin "e32") (pinfunction "e32_e32") (pintype "bidirectional"))
      (node (ref "J2") (pin "e35") (pinfunction "e35_e35") (pintype "bidirectional"))
      (node (ref "J2") (pin "e38") (pinfunction "e38_e38") (pintype "bidirectional"))
      (node (ref "J2") (pin "e4") (pinfunction "e4_e4") (pintype "bidirectional"))
      (node (ref "J2") (pin "e40") (pinfunction "e40_e40") (pintype "bidirectional"))
      (node (ref "J2") (pin "e5") (pinfunction "e5_e5") (pintype "bidirectional"))
      (node (ref "J2") (pin "e8") (pinfunction "e8_e8") (pintype "bidirectional"))
      (node (ref "J2") (pin "f12") (pinfunction "f12_f12") (pintype "bidirectional"))
      (node (ref "J2") (pin "f15") (pinfunction "f15_f15") (pintype "bidirectional"))
      (node (ref "J2") (pin "f18") (pinfunction "f18_f18") (pintype "bidirectional"))
      (node (ref "J2") (pin "f2") (pinfunction "f2_f2") (pintype "bidirectional"))
      (node (ref "J2") (pin "f21") (pinfunction "f21_f21") (pintype "bidirectional"))
      (node (ref "J2") (pin "f24") (pinfunction "f24_f24") (pintype "bidirectional"))
      (node (ref "J2") (pin "f27") (pinfunction "f27_f27") (pintype "bidirectional"))
      (node (ref "J2") (pin "f3") (pinfunction "f3_f3") (pintype "bidirectional"))
      (node (ref "J2") (pin "f30") (pinfunction "f30_f30") (pintype "bidirectional"))
      (node (ref "J2") (pin "f33") (pinfunction "f33_f33") (pintype "bidirectional"))
      (node (ref "J2") (pin "f36") (pinfunction "f36_f36") (pintype "bidirectional"))
      (node (ref "J2") (pin "f39") (pinfunction "f39_f39") (pintype "bidirectional"))
      (node (ref "J2") (pin "f6") (pinfunction "f6_f6") (pintype "bidirectional"))
      (node (ref "J2") (pin "f9") (pinfunction "f9_f9") (pintype "bidirectional"))
      (node (ref "J2") (pin "g1") (pinfunction "g1_g1") (pintype "bidirectional"))
      (node (ref "J2") (pin "g11") (pinfunction "g11_g11") (pintype "bidirectional"))
      (node (ref "J2") (pin "g14") (pinfunction "g14_g14") (pintype "bidirectional"))
      (node (ref "J2") (pin "g17") (pinfunction "g17_g17") (pintype "bidirectional"))
      (node (ref "J2") (pin "g20") (pinfunction "g20_g20") (pintype "bidirectional"))
      (node (ref "J2") (pin "g23") (pinfunction "g23_g23") (pintype "bidirectional"))
      (node (ref "J2") (pin "g26") (pinfunction "g26_g26") (pintype "bidirectional"))
      (node (ref "J2") (pin "g29") (pinfunction "g29_g29") (pintype "bidirectional"))
      (node (ref "J2") (pin "g32") (pinfunction "g32_g32") (pintype "bidirectional"))
      (node (ref "J2") (pin "g35") (pinfunction "g35_g35") (pintype "bidirectional"))
      (node (ref "J2") (pin "g38") (pinfunction "g38_g38") (pintype "bidirectional"))
      (node (ref "J2") (pin "g4") (pinfunction "g4_g4") (pintype "bidirectional"))
      (node (ref "J2") (pin "g40") (pinfunction "g40_g40") (pintype "bidirectional"))
      (node (ref "J2") (pin "g5") (pinfunction "g5_g5") (pintype "bidirectional"))
      (node (ref "J2") (pin "g8") (pinfunction "g8_g8") (pintype "bidirectional"))
      (node (ref "J2") (pin "h12") (pinfunction "h12_h12") (pintype "bidirectional"))
      (node (ref "J2") (pin "h15") (pinfunction "h15_h15") (pintype "bidirectional"))
      (node (ref "J2") (pin "h18") (pinfunction "h18_h18") (pintype "bidirectional"))
      (node (ref "J2") (pin "h21") (pinfunction "h21_h21") (pintype "bidirectional"))
      (node (ref "J2") (pin "h24") (pinfunction "h24_h24") (pintype "bidirectional"))
      (node (ref "J2") (pin "h27") (pinfunction "h27_h27") (pintype "bidirectional"))
      (node (ref "J2") (pin "h3") (pinfunction "h3_h3") (pintype "bidirectional"))
      (node (ref "J2") (pin "h30") (pinfunction "h30_h30") (pintype "bidirectional"))
      (node (ref "J2") (pin "h33") (pinfunction "h33_h33") (pintype "bidirectional"))
      (node (ref "J2") (pin "h36") (pinfunction "h36_h36") (pintype "bidirectional"))
      (node (ref "J2") (pin "h39") (pinfunction "h39_h39") (pintype "bidirectional"))
      (node (ref "J2") (pin "h6") (pinfunction "h6_h6") (pintype "bidirectional"))
      (node (ref "J2") (pin "h9") (pinfunction "h9_h9") (pintype "bidirectional"))
      (node (ref "J2") (pin "j1") (pinfunction "j1_j1") (pintype "bidirectional"))
      (node (ref "J2") (pin "j11") (pinfunction "j11_j11") (pintype "bidirectional"))
      (node (ref "J2") (pin "j14") (pinfunction "j14_j14") (pintype "bidirectional"))
      (node (ref "J2") (pin "j17") (pinfunction "j17_j17") (pintype "bidirectional"))
      (node (ref "J2") (pin "j20") (pinfunction "j20_j20") (pintype "bidirectional"))
      (node (ref "J2") (pin "j23") (pinfunction "j23_j23") (pintype "bidirectional"))
      (node (ref "J2") (pin "j26") (pinfunction "j26_j26") (pintype "bidirectional"))
      (node (ref "J2") (pin "j29") (pinfunction "j29_j29") (pintype "bidirectional"))
      (node (ref "J2") (pin "j32") (pinfunction "j32_j32") (pintype "bidirectional"))
      (node (ref "J2") (pin "j35") (pinfunction "j35_j35") (pintype "bidirectional"))
      (node (ref "J2") (pin "j38") (pinfunction "j38_j38") (pintype "bidirectional"))
      (node (ref "J2") (pin "j4") (pinfunction "j4_j4") (pintype "bidirectional"))
      (node (ref "J2") (pin "j40") (pinfunction "j40_j40") (pintype "bidirectional"))
      (node (ref "J2") (pin "j5") (pinfunction "j5_j5") (pintype "bidirectional"))
      (node (ref "J2") (pin "j8") (pinfunction "j8_j8") (pintype "bidirectional"))
      (node (ref "J2") (pin "k12") (pinfunction "k12_k12") (pintype "bidirectional"))
      (node (ref "J2") (pin "k15") (pinfunction "k15_k15") (pintype "bidirectional"))
      (node (ref "J2") (pin "k18") (pinfunction "k18_k18") (pintype "bidirectional"))
      (node (ref "J2") (pin "k2") (pinfunction "k2_k2") (pintype "bidirectional"))
      (node (ref "J2") (pin "k21") (pinfunction "k21_k21") (pintype "bidirectional"))
      (node (ref "J2") (pin "k24") (pinfunction "k24_k24") (pintype "bidirectional"))
      (node (ref "J2") (pin "k27") (pinfunction "k27_k27") (pintype "bidirectional"))
      (node (ref "J2") (pin "k3") (pinfunction "k3_k3") (pintype "bidirectional"))
      (node (ref "J2") (pin "k30") (pinfunction "k30_k30") (pintype "bidirectional"))
      (node (ref "J2") (pin "k33") (pinfunction "k33_k33") (pintype "bidirectional"))
      (node (ref "J2") (pin "k36") (pinfunction "k36_k36") (pintype "bidirectional"))
      (node (ref "J2") (pin "k39") (pinfunction "k39_k39") (pintype "bidirectional"))
      (node (ref "J2") (pin "k6") (pinfunction "k6_k6") (pintype "bidirectional"))
      (node (ref "J2") (pin "k9") (pinfunction "k9_k9") (pintype "bidirectional"))
    )
    (net (code "256") (name "unconnected-(J2-Padb40)") (class "Default")
      (node (ref "J2") (pin "b40") (pinfunction "b40_b40") (pintype "bidirectional"))
    )
  )
)
